# schematic.net
KiCad netlist of a schematic drawn in EasyEDA
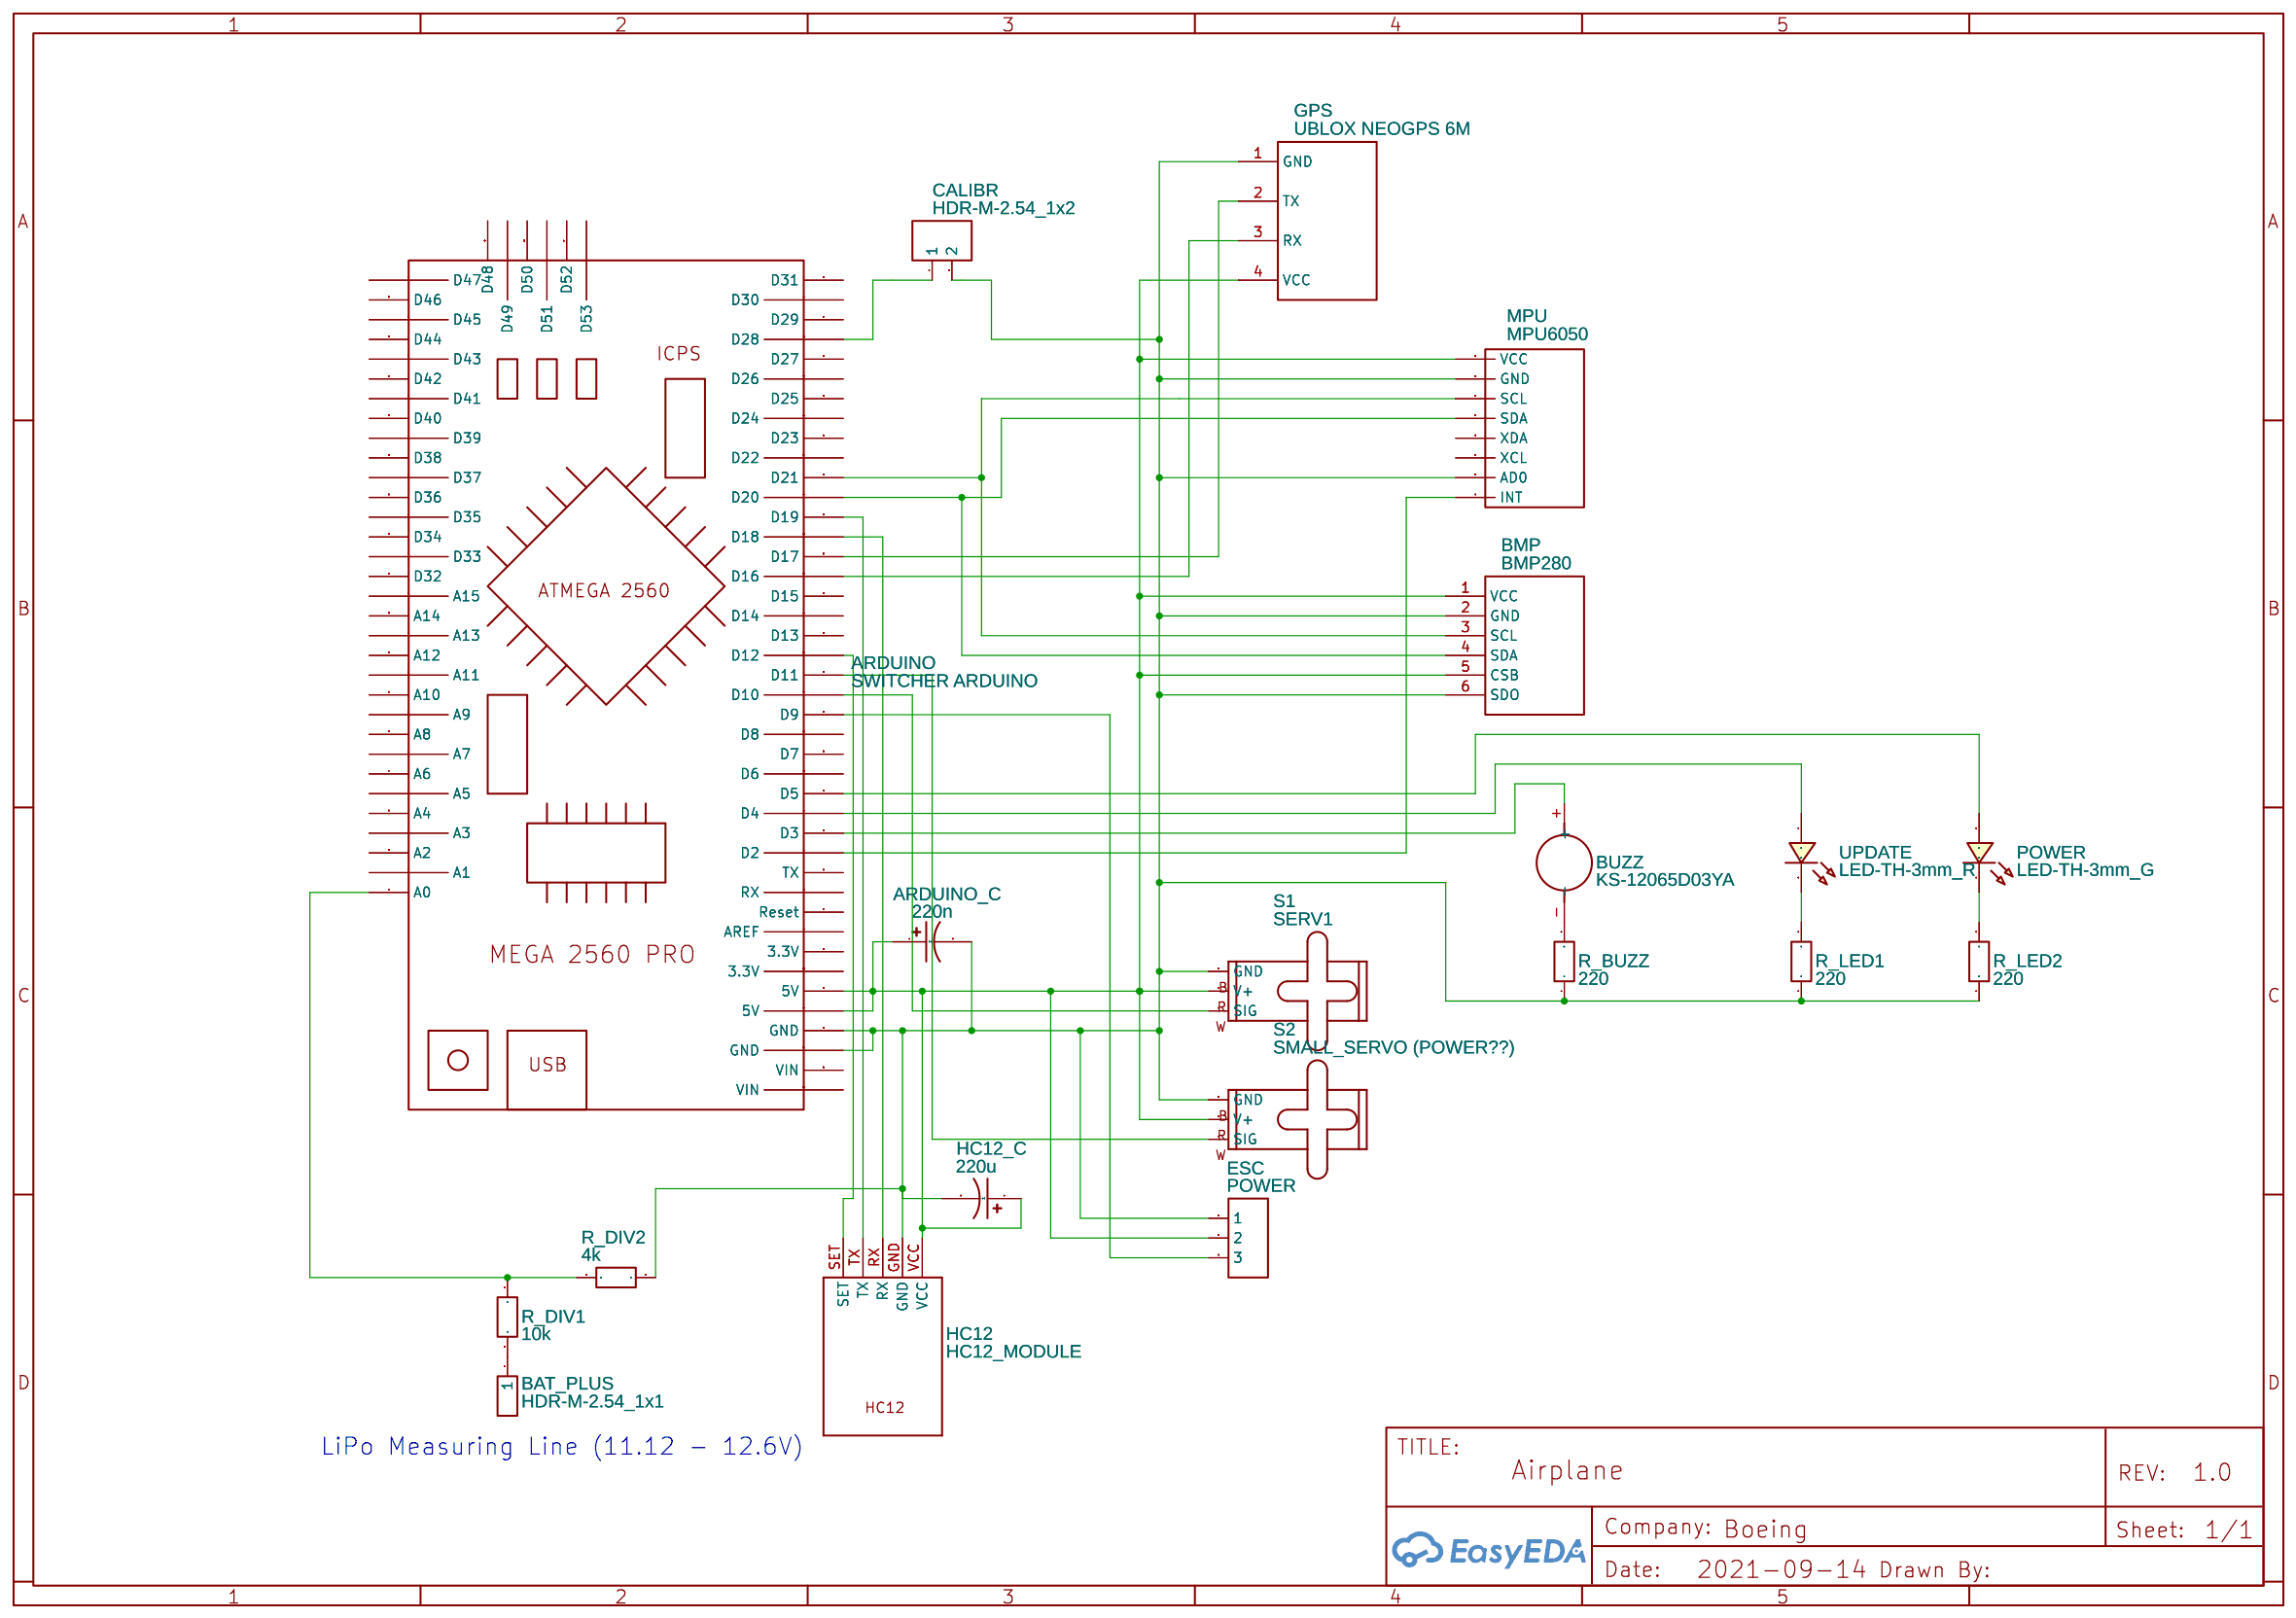
[diagram p0: schematic sheet]

(export (version "E")
  (design (tool "Eeschema 10.0.6"))
  (components
    (comp (ref "ARDUINO")
      (value "SWITCHER ARDUINO")
      (fields (field (name "BOM_Manufacturer Part") "Arduino Mega 2560 Pro Mini"))
      (libsource (lib "") (part "SWITCHER ARDUINO"))
    )
    (comp (ref "ARDUINO_C") (value "220n") (libsource (lib "") (part "CE_TH_D3.0×F1.5_US_1")))
    (comp (ref "BAT_PLUS")
      (value "HDR-M-2.54_1x1")
      (fields (field (name "BOM_Supplier Part") "C81276"))
      (libsource (lib "") (part "HDR-M-2.54_1x1"))
    )
    (comp (ref "BMP")
      (value "BMP280")
      (fields (field (name "BOM_Manufacturer Part") "MPU-6050"))
      (libsource (lib "") (part "BMP280"))
    )
    (comp (ref "BUZZ") (value "KS-12065D03YA") (libsource (lib "") (part "KS-12065D03YA")))
    (comp (ref "CALIBR")
      (value "HDR-M-2.54_1x2")
      (fields (field (name "BOM_Supplier Part") "C124375"))
      (libsource (lib "") (part "HDR-M-2.54_1x2"))
    )
    (comp (ref "ESC")
      (value "POWER")
      (fields (field (name "BOM_Supplier Part") "C180248"))
      (libsource (lib "") (part "HDR-M-2.54_1x3"))
    )
    (comp (ref "GPS") (value "UBLOX NEOGPS 6M") (libsource (lib "") (part "UBLOX NEOGPS 6M")))
    (comp (ref "HC12") (value "HC12_MODULE") (libsource (lib "") (part "HC12_MODULE")))
    (comp (ref "HC12_C") (value "220u") (libsource (lib "") (part "CE_TH_D3.0×F1.5_US")))
    (comp (ref "MPU") (value "MPU6050") (libsource (lib "") (part "MPU6050")))
    (comp (ref "POWER")
      (value "LED-TH-3mm_G")
      (fields
        (field (name "BOM_Manufacturer Part") "204-10SYGD/S530-E3")
        (field (name "BOM_Supplier Part") "C85161")
      )
      (libsource (lib "") (part "LED-TH-3mm_G"))
    )
    (comp (ref "R_BUZZ") (value "220") (libsource (lib "") (part "R_AXIAL-0.3_EU_1")))
    (comp (ref "R_DIV1") (value "10k") (libsource (lib "") (part "R_AXIAL-0.3_EU_3")))
    (comp (ref "R_DIV2") (value "4k") (libsource (lib "") (part "R_AXIAL-0.3_EU_2")))
    (comp (ref "R_LED1") (value "220") (libsource (lib "") (part "R_AXIAL-0.3_EU")))
    (comp (ref "R_LED2") (value "220") (libsource (lib "") (part "R_AXIAL-0.3_EU")))
    (comp (ref "S1") (value "SERV1") (libsource (lib "") (part "SMALL_SERVO")))
    (comp (ref "S2") (value "SMALL_SERVO (POWER??)") (libsource (lib "") (part "SMALL_SERVO")))
    (comp (ref "UPDATE")
      (value "LED-TH-3mm_R")
      (fields
        (field (name "BOM_Manufacturer Part") "204-10SDRD/S530-A3-L")
        (field (name "BOM_Supplier Part") "C84774")
      )
      (libsource (lib "") (part "LED-TH-3mm_R"))
    )
  )
  (nets
    (net (code "1") (name "Net-(ARDUINO-A0)") (class "Default")
      (node (ref "ARDUINO") (pin "1") (pinfunction "A0_1") (pintype "unspecified"))
      (node (ref "R_DIV1") (pin "1") (pinfunction "1_1") (pintype "unspecified"))
      (node (ref "R_DIV2") (pin "2") (pinfunction "2_2") (pintype "unspecified"))
    )
    (net (code "2") (name "Net-(ARDUINO-D2)") (class "Default")
      (node (ref "ARDUINO") (pin "74") (pinfunction "D2_74") (pintype "unspecified"))
      (node (ref "MPU") (pin "INT") (pinfunction "INT_INT") (pintype "unspecified"))
    )
    (net (code "3") (name "Net-(ARDUINO-D3)") (class "Default")
      (node (ref "ARDUINO") (pin "73") (pinfunction "D3_73") (pintype "unspecified"))
      (node (ref "BUZZ") (pin "+") (pinfunction "+_+") (pintype "unspecified"))
    )
    (net (code "4") (name "Net-(ARDUINO-D4)") (class "Default")
      (node (ref "ARDUINO") (pin "72") (pinfunction "D4_72") (pintype "unspecified"))
      (node (ref "UPDATE") (pin "1") (pinfunction "1_1") (pintype "unspecified"))
    )
    (net (code "5") (name "Net-(ARDUINO-D5)") (class "Default")
      (node (ref "ARDUINO") (pin "71") (pinfunction "D5_71") (pintype "unspecified"))
      (node (ref "POWER") (pin "1") (pinfunction "1_1") (pintype "unspecified"))
    )
    (net (code "6") (name "Net-(ARDUINO-D9)") (class "Default")
      (node (ref "ARDUINO") (pin "67") (pinfunction "D9_67") (pintype "unspecified"))
      (node (ref "ESC") (pin "3") (pinfunction "3_3") (pintype "input"))
    )
    (net (code "7") (name "Net-(ARDUINO-D10)") (class "Default")
      (node (ref "ARDUINO") (pin "66") (pinfunction "D10_66") (pintype "unspecified"))
      (node (ref "S1") (pin "1") (pinfunction "SIG_1") (pintype "unspecified"))
    )
    (net (code "8") (name "Net-(ARDUINO-D11)") (class "Default")
      (node (ref "ARDUINO") (pin "65") (pinfunction "D11_65") (pintype "unspecified"))
      (node (ref "S2") (pin "1") (pinfunction "SIG_1") (pintype "unspecified"))
    )
    (net (code "9") (name "Net-(ARDUINO-D12)") (class "Default")
      (node (ref "ARDUINO") (pin "64") (pinfunction "D12_64") (pintype "unspecified"))
      (node (ref "HC12") (pin "SET") (pinfunction "SET_SET") (pintype "bidirectional"))
    )
    (net (code "10") (name "Net-(ARDUINO-D16)") (class "Default")
      (node (ref "ARDUINO") (pin "60") (pinfunction "D16_60") (pintype "unspecified"))
      (node (ref "GPS") (pin "3") (pinfunction "RX_3") (pintype "unspecified"))
    )
    (net (code "11") (name "Net-(ARDUINO-D17)") (class "Default")
      (node (ref "ARDUINO") (pin "59") (pinfunction "D17_59") (pintype "unspecified"))
      (node (ref "GPS") (pin "2") (pinfunction "TX_2") (pintype "unspecified"))
    )
    (net (code "12") (name "Net-(ARDUINO-D18)") (class "Default")
      (node (ref "ARDUINO") (pin "58") (pinfunction "D18_58") (pintype "unspecified"))
      (node (ref "HC12") (pin "RX") (pinfunction "RX_RX") (pintype "bidirectional"))
    )
    (net (code "13") (name "Net-(ARDUINO-D19)") (class "Default")
      (node (ref "ARDUINO") (pin "57") (pinfunction "D19_57") (pintype "unspecified"))
      (node (ref "HC12") (pin "TX") (pinfunction "TX_TX") (pintype "bidirectional"))
    )
    (net (code "14") (name "Net-(ARDUINO-D20)") (class "Default")
      (node (ref "ARDUINO") (pin "56") (pinfunction "D20_56") (pintype "unspecified"))
      (node (ref "BMP") (pin "4") (pinfunction "SDA_4") (pintype "unspecified"))
      (node (ref "MPU") (pin "SDA") (pinfunction "SDA_SDA") (pintype "unspecified"))
    )
    (net (code "15") (name "Net-(ARDUINO-D21)") (class "Default")
      (node (ref "ARDUINO") (pin "55") (pinfunction "D21_55") (pintype "unspecified"))
      (node (ref "BMP") (pin "3") (pinfunction "SCL_3") (pintype "unspecified"))
      (node (ref "MPU") (pin "SCL") (pinfunction "SCL_SCL") (pintype "unspecified"))
    )
    (net (code "16") (name "Net-(ARDUINO-D28)") (class "Default")
      (node (ref "ARDUINO") (pin "48") (pinfunction "D28_48") (pintype "unspecified"))
      (node (ref "CALIBR") (pin "1") (pinfunction "1_1") (pintype "unspecified"))
    )
    (net (code "17") (name "Net-(BAT_PLUS-Pad1)") (class "Default")
      (node (ref "BAT_PLUS") (pin "1") (pinfunction "1_1") (pintype "input"))
      (node (ref "R_DIV1") (pin "2") (pinfunction "2_2") (pintype "unspecified"))
    )
    (net (code "18") (name "Net-(BMP-CSB)") (class "Default")
      (node (ref "ARDUINO") (pin "81") (pinfunction "5V_81") (pintype "unspecified"))
      (node (ref "ARDUINO") (pin "82") (pinfunction "5V_82") (pintype "unspecified"))
      (node (ref "ARDUINO_C") (pin "1") (pinfunction "1_1") (pintype "unspecified"))
      (node (ref "BMP") (pin "1") (pinfunction "VCC_1") (pintype "unspecified"))
      (node (ref "BMP") (pin "5") (pinfunction "CSB_5") (pintype "unspecified"))
      (node (ref "ESC") (pin "2") (pinfunction "2_2") (pintype "input"))
      (node (ref "GPS") (pin "4") (pinfunction "VCC_4") (pintype "unspecified"))
      (node (ref "HC12") (pin "VCC") (pinfunction "VCC_VCC") (pintype "bidirectional"))
      (node (ref "HC12_C") (pin "1") (pinfunction "1_1") (pintype "unspecified"))
      (node (ref "MPU") (pin "VCC") (pinfunction "VCC_VCC") (pintype "unspecified"))
      (node (ref "S1") (pin "2") (pinfunction "V+_2") (pintype "unspecified"))
      (node (ref "S2") (pin "2") (pinfunction "V+_2") (pintype "unspecified"))
    )
    (net (code "19") (name "Net-(BMP-GND)") (class "Default")
      (node (ref "ARDUINO") (pin "83") (pinfunction "GND_83") (pintype "unspecified"))
      (node (ref "ARDUINO") (pin "84") (pinfunction "GND_84") (pintype "unspecified"))
      (node (ref "ARDUINO_C") (pin "2") (pinfunction "2_2") (pintype "unspecified"))
      (node (ref "BMP") (pin "2") (pinfunction "GND_2") (pintype "unspecified"))
      (node (ref "BMP") (pin "6") (pinfunction "SDO_6") (pintype "unspecified"))
      (node (ref "CALIBR") (pin "2") (pinfunction "2_2") (pintype "unspecified"))
      (node (ref "ESC") (pin "1") (pinfunction "1_1") (pintype "input"))
      (node (ref "GPS") (pin "1") (pinfunction "GND_1") (pintype "unspecified"))
      (node (ref "HC12") (pin "GND") (pinfunction "GND_GND") (pintype "bidirectional"))
      (node (ref "HC12_C") (pin "2") (pinfunction "2_2") (pintype "unspecified"))
      (node (ref "MPU") (pin "AD0") (pinfunction "AD0_AD0") (pintype "unspecified"))
      (node (ref "MPU") (pin "GND") (pinfunction "GND_GND") (pintype "unspecified"))
      (node (ref "R_BUZZ") (pin "1") (pinfunction "1_1") (pintype "unspecified"))
      (node (ref "R_DIV2") (pin "1") (pinfunction "1_1") (pintype "unspecified"))
      (node (ref "R_LED1") (pin "1") (pinfunction "1_1") (pintype "unspecified"))
      (node (ref "R_LED2") (pin "1") (pinfunction "1_1") (pintype "unspecified"))
      (node (ref "S1") (pin "3") (pinfunction "GND_3") (pintype "unspecified"))
      (node (ref "S2") (pin "3") (pinfunction "GND_3") (pintype "unspecified"))
    )
    (net (code "20") (name "Net-(BUZZ-Pad-)") (class "Default")
      (node (ref "BUZZ") (pin "-") (pinfunction "-_-") (pintype "unspecified"))
      (node (ref "R_BUZZ") (pin "2") (pinfunction "2_2") (pintype "unspecified"))
    )
    (net (code "21") (name "Net-(POWER-Pad2)") (class "Default")
      (node (ref "POWER") (pin "2") (pinfunction "2_2") (pintype "unspecified"))
      (node (ref "R_LED2") (pin "2") (pinfunction "2_2") (pintype "unspecified"))
    )
    (net (code "22") (name "Net-(R_LED1-Pad2)") (class "Default")
      (node (ref "R_LED1") (pin "2") (pinfunction "2_2") (pintype "unspecified"))
      (node (ref "UPDATE") (pin "2") (pinfunction "2_2") (pintype "unspecified"))
    )
    (net (code "23") (name "unconnected-(ARDUINO-3.3V-Pad79)") (class "Default")
      (node (ref "ARDUINO") (pin "79") (pinfunction "3.3V_79") (pintype "unspecified"))
    )
    (net (code "24") (name "unconnected-(ARDUINO-3.3V-Pad80)") (class "Default")
      (node (ref "ARDUINO") (pin "80") (pinfunction "3.3V_80") (pintype "unspecified"))
    )
    (net (code "25") (name "unconnected-(ARDUINO-A1-Pad2)") (class "Default")
      (node (ref "ARDUINO") (pin "2") (pinfunction "A1_2") (pintype "unspecified"))
    )
    (net (code "26") (name "unconnected-(ARDUINO-A2-Pad3)") (class "Default")
      (node (ref "ARDUINO") (pin "3") (pinfunction "A2_3") (pintype "unspecified"))
    )
    (net (code "27") (name "unconnected-(ARDUINO-A3-Pad4)") (class "Default")
      (node (ref "ARDUINO") (pin "4") (pinfunction "A3_4") (pintype "unspecified"))
    )
    (net (code "28") (name "unconnected-(ARDUINO-A4-Pad5)") (class "Default")
      (node (ref "ARDUINO") (pin "5") (pinfunction "A4_5") (pintype "unspecified"))
    )
    (net (code "29") (name "unconnected-(ARDUINO-A5-Pad6)") (class "Default")
      (node (ref "ARDUINO") (pin "6") (pinfunction "A5_6") (pintype "unspecified"))
    )
    (net (code "30") (name "unconnected-(ARDUINO-A6-Pad7)") (class "Default")
      (node (ref "ARDUINO") (pin "7") (pinfunction "A6_7") (pintype "unspecified"))
    )
    (net (code "31") (name "unconnected-(ARDUINO-A7-Pad8)") (class "Default")
      (node (ref "ARDUINO") (pin "8") (pinfunction "A7_8") (pintype "unspecified"))
    )
    (net (code "32") (name "unconnected-(ARDUINO-A8-Pad9)") (class "Default")
      (node (ref "ARDUINO") (pin "9") (pinfunction "A8_9") (pintype "unspecified"))
    )
    (net (code "33") (name "unconnected-(ARDUINO-A9-Pad10)") (class "Default")
      (node (ref "ARDUINO") (pin "10") (pinfunction "A9_10") (pintype "unspecified"))
    )
    (net (code "34") (name "unconnected-(ARDUINO-A10-Pad11)") (class "Default")
      (node (ref "ARDUINO") (pin "11") (pinfunction "A10_11") (pintype "unspecified"))
    )
    (net (code "35") (name "unconnected-(ARDUINO-A11-Pad12)") (class "Default")
      (node (ref "ARDUINO") (pin "12") (pinfunction "A11_12") (pintype "unspecified"))
    )
    (net (code "36") (name "unconnected-(ARDUINO-A12-Pad13)") (class "Default")
      (node (ref "ARDUINO") (pin "13") (pinfunction "A12_13") (pintype "unspecified"))
    )
    (net (code "37") (name "unconnected-(ARDUINO-A13-Pad14)") (class "Default")
      (node (ref "ARDUINO") (pin "14") (pinfunction "A13_14") (pintype "unspecified"))
    )
    (net (code "38") (name "unconnected-(ARDUINO-A14-Pad15)") (class "Default")
      (node (ref "ARDUINO") (pin "15") (pinfunction "A14_15") (pintype "unspecified"))
    )
    (net (code "39") (name "unconnected-(ARDUINO-A15-Pad16)") (class "Default")
      (node (ref "ARDUINO") (pin "16") (pinfunction "A15_16") (pintype "unspecified"))
    )
    (net (code "40") (name "unconnected-(ARDUINO-AREF-Pad78)") (class "Default")
      (node (ref "ARDUINO") (pin "78") (pinfunction "AREF_78") (pintype "unspecified"))
    )
    (net (code "41") (name "unconnected-(ARDUINO-D6-Pad70)") (class "Default")
      (node (ref "ARDUINO") (pin "70") (pinfunction "D6_70") (pintype "unspecified"))
    )
    (net (code "42") (name "unconnected-(ARDUINO-D7-Pad69)") (class "Default")
      (node (ref "ARDUINO") (pin "69") (pinfunction "D7_69") (pintype "unspecified"))
    )
    (net (code "43") (name "unconnected-(ARDUINO-D8-Pad68)") (class "Default")
      (node (ref "ARDUINO") (pin "68") (pinfunction "D8_68") (pintype "unspecified"))
    )
    (net (code "44") (name "unconnected-(ARDUINO-D13-Pad63)") (class "Default")
      (node (ref "ARDUINO") (pin "63") (pinfunction "D13_63") (pintype "unspecified"))
    )
    (net (code "45") (name "unconnected-(ARDUINO-D14-Pad62)") (class "Default")
      (node (ref "ARDUINO") (pin "62") (pinfunction "D14_62") (pintype "unspecified"))
    )
    (net (code "46") (name "unconnected-(ARDUINO-D15-Pad61)") (class "Default")
      (node (ref "ARDUINO") (pin "61") (pinfunction "D15_61") (pintype "unspecified"))
    )
    (net (code "47") (name "unconnected-(ARDUINO-D22-Pad54)") (class "Default")
      (node (ref "ARDUINO") (pin "54") (pinfunction "D22_54") (pintype "unspecified"))
    )
    (net (code "48") (name "unconnected-(ARDUINO-D23-Pad53)") (class "Default")
      (node (ref "ARDUINO") (pin "53") (pinfunction "D23_53") (pintype "unspecified"))
    )
    (net (code "49") (name "unconnected-(ARDUINO-D24-Pad52)") (class "Default")
      (node (ref "ARDUINO") (pin "52") (pinfunction "D24_52") (pintype "unspecified"))
    )
    (net (code "50") (name "unconnected-(ARDUINO-D25-Pad51)") (class "Default")
      (node (ref "ARDUINO") (pin "51") (pinfunction "D25_51") (pintype "unspecified"))
    )
    (net (code "51") (name "unconnected-(ARDUINO-D26-Pad50)") (class "Default")
      (node (ref "ARDUINO") (pin "50") (pinfunction "D26_50") (pintype "unspecified"))
    )
    (net (code "52") (name "unconnected-(ARDUINO-D27-Pad49)") (class "Default")
      (node (ref "ARDUINO") (pin "49") (pinfunction "D27_49") (pintype "unspecified"))
    )
    (net (code "53") (name "unconnected-(ARDUINO-D29-Pad47)") (class "Default")
      (node (ref "ARDUINO") (pin "47") (pinfunction "D29_47") (pintype "unspecified"))
    )
    (net (code "54") (name "unconnected-(ARDUINO-D30-Pad46)") (class "Default")
      (node (ref "ARDUINO") (pin "46") (pinfunction "D30_46") (pintype "unspecified"))
    )
    (net (code "55") (name "unconnected-(ARDUINO-D31-Pad45)") (class "Default")
      (node (ref "ARDUINO") (pin "45") (pinfunction "D31_45") (pintype "unspecified"))
    )
    (net (code "56") (name "unconnected-(ARDUINO-D32-Pad17)") (class "Default")
      (node (ref "ARDUINO") (pin "17") (pinfunction "D32_17") (pintype "unspecified"))
    )
    (net (code "57") (name "unconnected-(ARDUINO-D33-Pad18)") (class "Default")
      (node (ref "ARDUINO") (pin "18") (pinfunction "D33_18") (pintype "unspecified"))
    )
    (net (code "58") (name "unconnected-(ARDUINO-D34-Pad19)") (class "Default")
      (node (ref "ARDUINO") (pin "19") (pinfunction "D34_19") (pintype "unspecified"))
    )
    (net (code "59") (name "unconnected-(ARDUINO-D35-Pad20)") (class "Default")
      (node (ref "ARDUINO") (pin "20") (pinfunction "D35_20") (pintype "unspecified"))
    )
    (net (code "60") (name "unconnected-(ARDUINO-D36-Pad21)") (class "Default")
      (node (ref "ARDUINO") (pin "21") (pinfunction "D36_21") (pintype "unspecified"))
    )
    (net (code "61") (name "unconnected-(ARDUINO-D37-Pad22)") (class "Default")
      (node (ref "ARDUINO") (pin "22") (pinfunction "D37_22") (pintype "unspecified"))
    )
    (net (code "62") (name "unconnected-(ARDUINO-D38-Pad23)") (class "Default")
      (node (ref "ARDUINO") (pin "23") (pinfunction "D38_23") (pintype "unspecified"))
    )
    (net (code "63") (name "unconnected-(ARDUINO-D39-Pad24)") (class "Default")
      (node (ref "ARDUINO") (pin "24") (pinfunction "D39_24") (pintype "unspecified"))
    )
    (net (code "64") (name "unconnected-(ARDUINO-D40-Pad25)") (class "Default")
      (node (ref "ARDUINO") (pin "25") (pinfunction "D40_25") (pintype "unspecified"))
    )
    (net (code "65") (name "unconnected-(ARDUINO-D41-Pad26)") (class "Default")
      (node (ref "ARDUINO") (pin "26") (pinfunction "D41_26") (pintype "unspecified"))
    )
    (net (code "66") (name "unconnected-(ARDUINO-D42-Pad27)") (class "Default")
      (node (ref "ARDUINO") (pin "27") (pinfunction "D42_27") (pintype "unspecified"))
    )
    (net (code "67") (name "unconnected-(ARDUINO-D43-Pad28)") (class "Default")
      (node (ref "ARDUINO") (pin "28") (pinfunction "D43_28") (pintype "unspecified"))
    )
    (net (code "68") (name "unconnected-(ARDUINO-D44-Pad29)") (class "Default")
      (node (ref "ARDUINO") (pin "29") (pinfunction "D44_29") (pintype "unspecified"))
    )
    (net (code "69") (name "unconnected-(ARDUINO-D45-Pad30)") (class "Default")
      (node (ref "ARDUINO") (pin "30") (pinfunction "D45_30") (pintype "unspecified"))
    )
    (net (code "70") (name "unconnected-(ARDUINO-D46-Pad31)") (class "Default")
      (node (ref "ARDUINO") (pin "31") (pinfunction "D46_31") (pintype "unspecified"))
    )
    (net (code "71") (name "unconnected-(ARDUINO-D47-Pad32)") (class "Default")
      (node (ref "ARDUINO") (pin "32") (pinfunction "D47_32") (pintype "unspecified"))
    )
    (net (code "72") (name "unconnected-(ARDUINO-D48-Pad33)") (class "Default")
      (node (ref "ARDUINO") (pin "33") (pinfunction "D48_33") (pintype "unspecified"))
    )
    (net (code "73") (name "unconnected-(ARDUINO-D49-Pad34)") (class "Default")
      (node (ref "ARDUINO") (pin "34") (pinfunction "D49_34") (pintype "unspecified"))
    )
    (net (code "74") (name "unconnected-(ARDUINO-D50-Pad35)") (class "Default")
      (node (ref "ARDUINO") (pin "35") (pinfunction "D50_35") (pintype "unspecified"))
    )
    (net (code "75") (name "unconnected-(ARDUINO-D51-Pad36)") (class "Default")
      (node (ref "ARDUINO") (pin "36") (pinfunction "D51_36") (pintype "unspecified"))
    )
    (net (code "76") (name "unconnected-(ARDUINO-D52-Pad37)") (class "Default")
      (node (ref "ARDUINO") (pin "37") (pinfunction "D52_37") (pintype "unspecified"))
    )
    (net (code "77") (name "unconnected-(ARDUINO-D53-Pad38)") (class "Default")
      (node (ref "ARDUINO") (pin "38") (pinfunction "D53_38") (pintype "unspecified"))
    )
    (net (code "78") (name "unconnected-(ARDUINO-RX-Pad76)") (class "Default")
      (node (ref "ARDUINO") (pin "76") (pinfunction "RX_76") (pintype "unspecified"))
    )
    (net (code "79") (name "unconnected-(ARDUINO-Reset-Pad77)") (class "Default")
      (node (ref "ARDUINO") (pin "77") (pinfunction "Reset_77") (pintype "unspecified"))
    )
    (net (code "80") (name "unconnected-(ARDUINO-TX-Pad75)") (class "Default")
      (node (ref "ARDUINO") (pin "75") (pinfunction "TX_75") (pintype "unspecified"))
    )
    (net (code "81") (name "unconnected-(ARDUINO-VIN-Pad85)") (class "Default")
      (node (ref "ARDUINO") (pin "85") (pinfunction "VIN_85") (pintype "unspecified"))
    )
    (net (code "82") (name "unconnected-(ARDUINO-VIN-Pad86)") (class "Default")
      (node (ref "ARDUINO") (pin "86") (pinfunction "VIN_86") (pintype "unspecified"))
    )
    (net (code "83") (name "unconnected-(MPU-PadXCL)") (class "Default")
      (node (ref "MPU") (pin "XCL") (pinfunction "XCL_XCL") (pintype "unspecified"))
    )
    (net (code "84") (name "unconnected-(MPU-PadXDA)") (class "Default")
      (node (ref "MPU") (pin "XDA") (pinfunction "XDA_XDA") (pintype "unspecified"))
    )
  )
)
